# Power_HK.net
KiCad netlist of a schematic drawn in Altium Designer
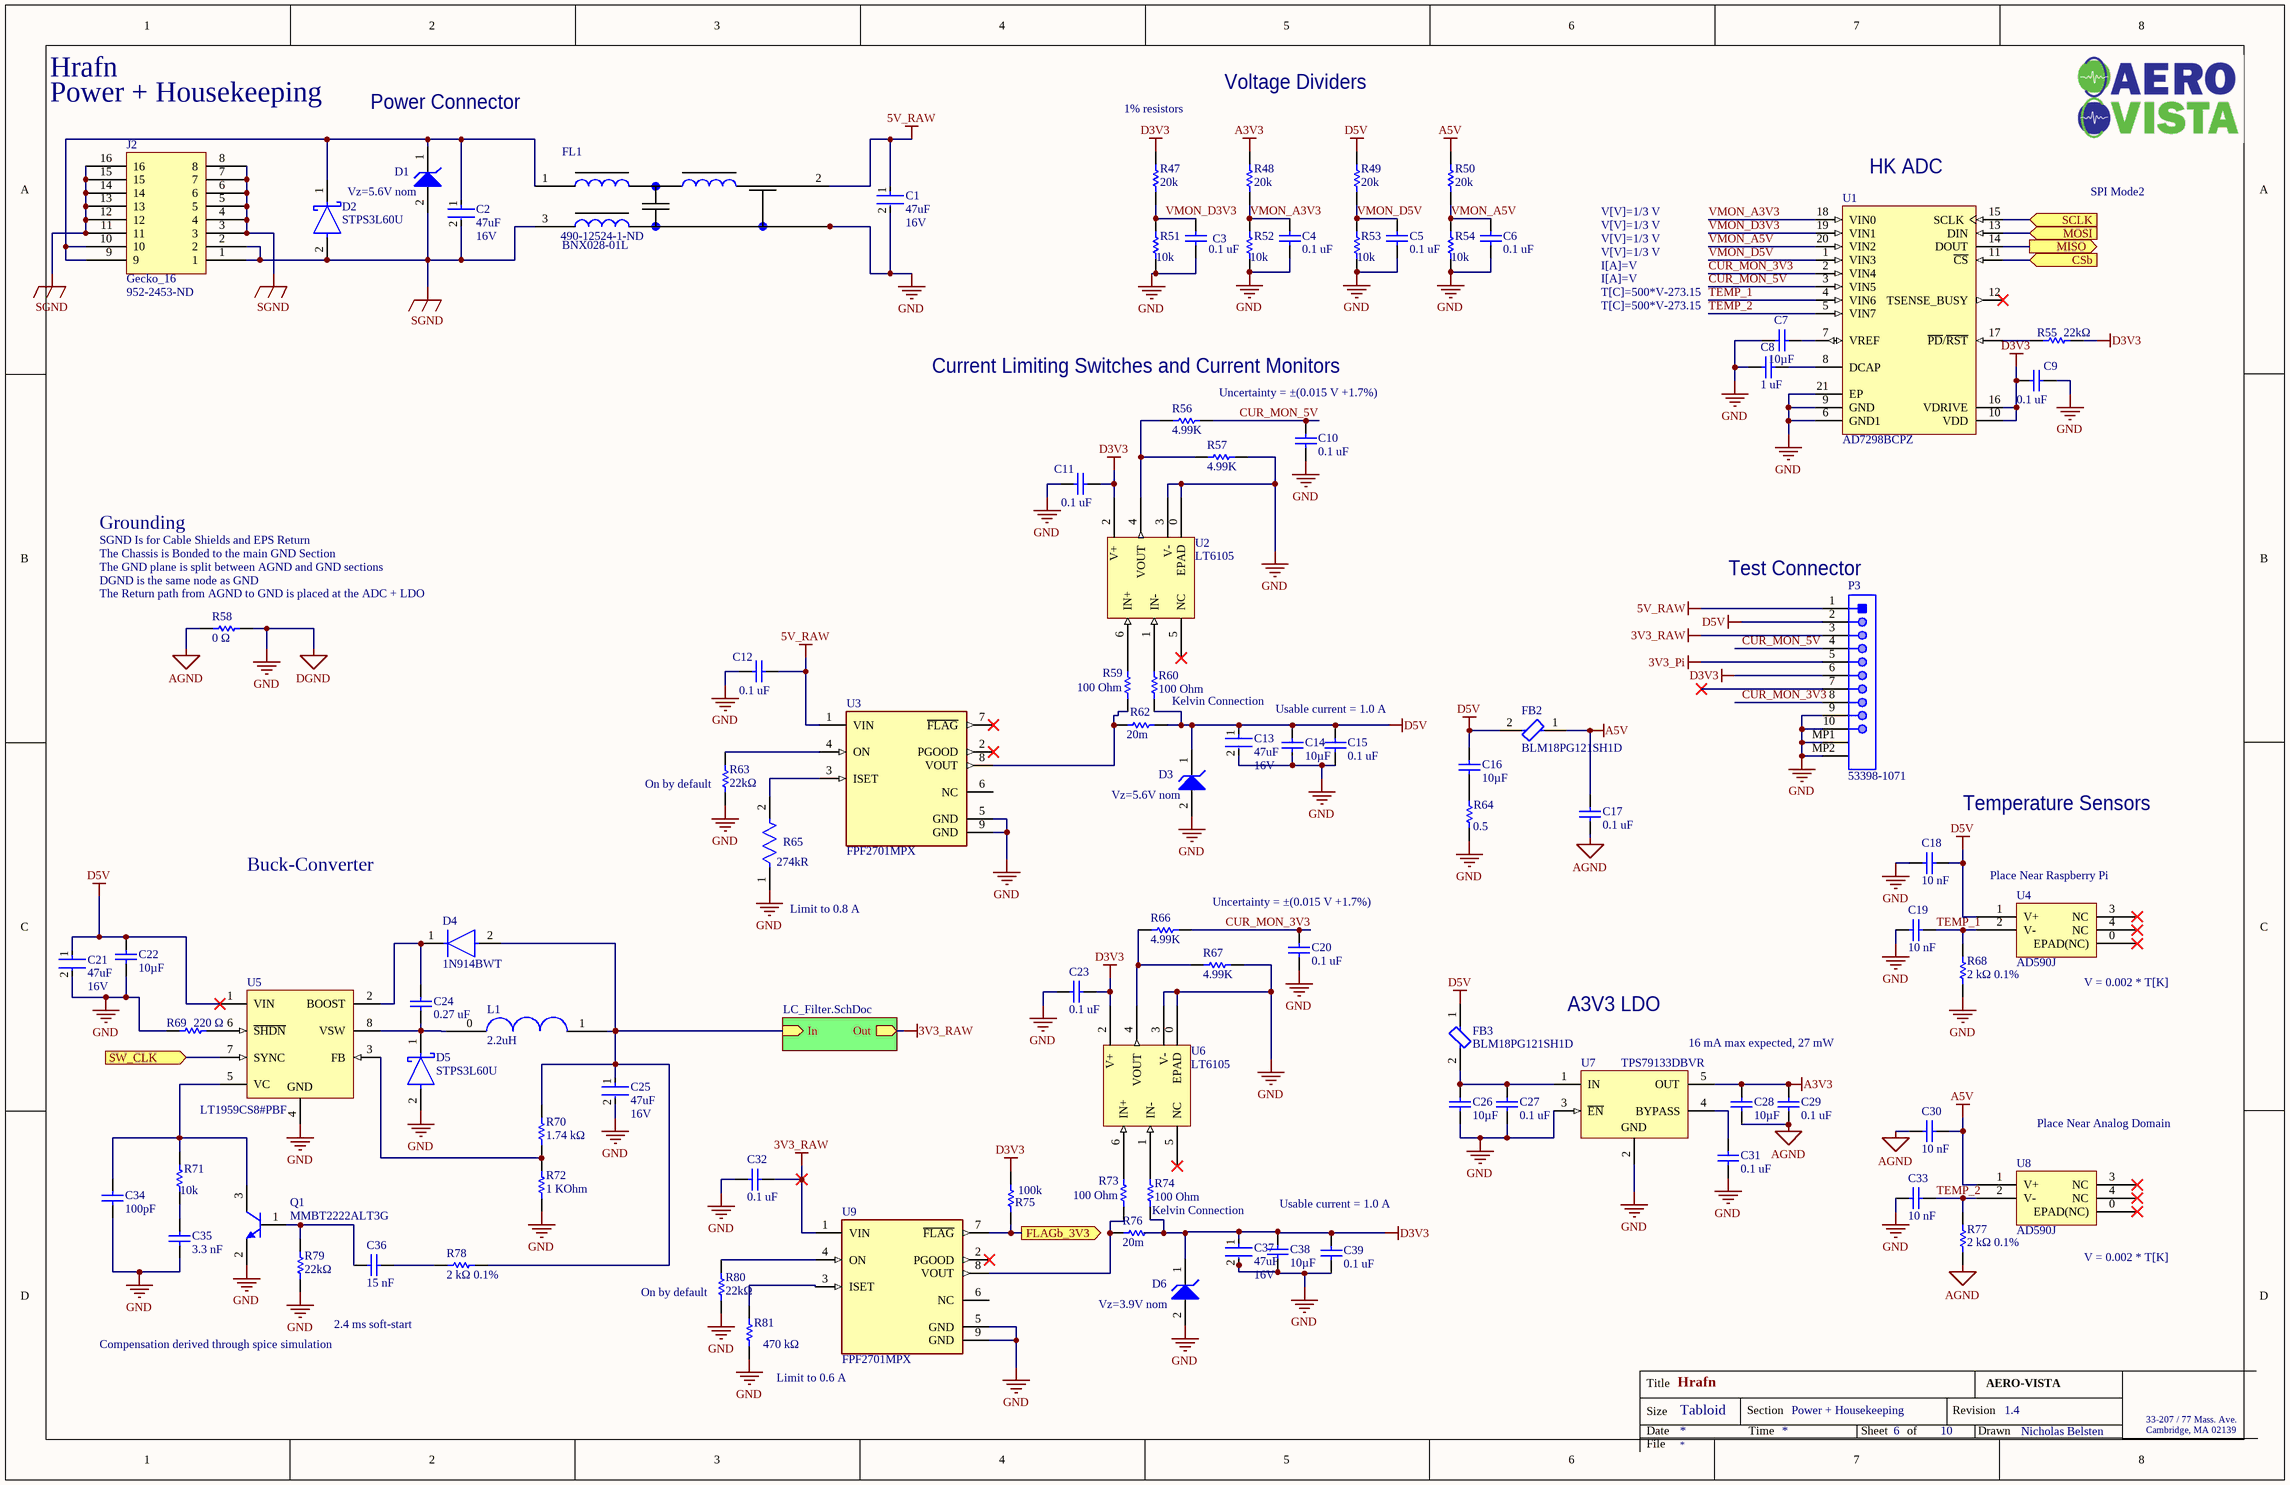
[diagram p0: Power_HK.SchDoc]

(export (version "E")
  (design (tool "Eeschema 10.0.6"))
  (components
    (comp (ref "C1")
      (value "GRT32EC81C476ME13L")
      (footprint "FP-GRT32E-0_3-IPC_C")
      (description "Multi-Layer Ceramic Capacitor 47uF 16V X6S ±20% 1210 Emboss T/R")
      (fields
        (field (name "CAPACITANCE") "47uF")
        (field (name "VOLTAGE RATING") "16V")
        (field (name "TOLERANCE") "20%")
      )
      (libsource (lib "Altium Content Vault") (part "02cd4be3c70576c341d710602a673aa"))
    )
    (comp (ref "C2")
      (value "GRT32EC81C476ME13L")
      (footprint "FP-GRT32E-0_3-IPC_C")
      (description "Multi-Layer Ceramic Capacitor 47uF 16V X6S ±20% 1210 Emboss T/R")
      (fields
        (field (name "CAPACITANCE") "47uF")
        (field (name "VOLTAGE RATING") "16V")
        (field (name "TOLERANCE") "20%")
      )
      (libsource (lib "Altium Content Vault") (part "02cd4be3c70576c341d710602a673aa"))
    )
    (comp (ref "C3")
      (value "0.1 uF")
      (footprint "CAPC0402(1005)60_L")
      (description "CAP 100nF 16V ±5% 0402 (1005 Metric) Thickness 0.6mm SMD")
      (fields (field (name "TOLERANCE") "Â±5%"))
      (libsource (lib "Altium Content Vault") (part "CAP"))
    )
    (comp (ref "C4")
      (value "0.1 uF")
      (footprint "CAPC0402(1005)60_L")
      (description "CAP 100nF 16V ±5% 0402 (1005 Metric) Thickness 0.6mm SMD")
      (fields (field (name "TOLERANCE") "Â±5%"))
      (libsource (lib "Altium Content Vault") (part "CAP"))
    )
    (comp (ref "C5")
      (value "0.1 uF")
      (footprint "CAPC0402(1005)60_L")
      (description "CAP 100nF 16V ±5% 0402 (1005 Metric) Thickness 0.6mm SMD")
      (fields (field (name "TOLERANCE") "Â±5%"))
      (libsource (lib "Altium Content Vault") (part "CAP"))
    )
    (comp (ref "C6")
      (value "0.1 uF")
      (footprint "CAPC0402(1005)60_L")
      (description "CAP 100nF 16V ±5% 0402 (1005 Metric) Thickness 0.6mm SMD")
      (fields (field (name "TOLERANCE") "Â±5%"))
      (libsource (lib "Altium Content Vault") (part "CAP"))
    )
    (comp (ref "C7")
      (value "EMK107BBJ106MA-T")
      (footprint "CAPC1608X100X35LL20T25")
      (description "Chip Capacitor, 10 uF, +/- 20%, 16 V, -55 to 85 degC, 0603 (1608 Metric), RoHS, Tape and Reel")
      (fields
        (field (name "CAPACITANCE") "10µF")
        (field (name "MANUFACTURER") "Taiyo Yuden")
        (field (name "TOLERANCE") "±20%")
      )
      (libsource (lib "Altium Content Vault") (part "CAP-NP-2"))
    )
    (comp (ref "C8")
      (value "1 uF")
      (footprint "CAPC1005X60X30NL05T10")
      (fields (field (name "PART NUMBER") "C0402C105M8PACTU") (field (name "MANUFACTURER") "Kemet"))
      (libsource (lib "Altium Content Vault") (part "CAP"))
    )
    (comp (ref "C9")
      (value "0.1 uF")
      (footprint "CAPC0402(1005)60_L")
      (description "CAP 100nF 16V ±5% 0402 (1005 Metric) Thickness 0.6mm SMD")
      (fields (field (name "TOLERANCE") "Â±5%"))
      (libsource (lib "Altium Content Vault") (part "CAP"))
    )
    (comp (ref "C10")
      (value "0.1 uF")
      (footprint "CAPC0402(1005)60_L")
      (description "CAP 100nF 16V ±5% 0402 (1005 Metric) Thickness 0.6mm SMD")
      (fields (field (name "TOLERANCE") "Â±5%"))
      (libsource (lib "Altium Content Vault") (part "CAP"))
    )
    (comp (ref "C11")
      (value "0.1 uF")
      (footprint "CAPC0402(1005)60_L")
      (description "CAP 100nF 16V ±5% 0402 (1005 Metric) Thickness 0.6mm SMD")
      (fields (field (name "TOLERANCE") "Â±5%"))
      (libsource (lib "Altium Content Vault") (part "CAP"))
    )
    (comp (ref "C12")
      (value "0.1 uF")
      (footprint "CAPC0402(1005)60_L")
      (description "CAP 100nF 16V ±5% 0402 (1005 Metric) Thickness 0.6mm SMD")
      (fields (field (name "TOLERANCE") "Â±5%"))
      (libsource (lib "Altium Content Vault") (part "CAP"))
    )
    (comp (ref "C13")
      (value "GRT32EC81C476ME13L")
      (footprint "FP-GRT32E-0_3-IPC_C")
      (description "Multi-Layer Ceramic Capacitor 47uF 16V X6S ±20% 1210 Emboss T/R")
      (fields
        (field (name "CAPACITANCE") "47uF")
        (field (name "VOLTAGE RATING") "16V")
        (field (name "TOLERANCE") "20%")
      )
      (libsource (lib "Altium Content Vault") (part "02cd4be3c70576c341d710602a673aa"))
    )
    (comp (ref "C14")
      (value "EMK107BBJ106MA-T")
      (footprint "CAPC1608X100X35LL20T25")
      (description "Chip Capacitor, 10 uF, +/- 20%, 16 V, -55 to 85 degC, 0603 (1608 Metric), RoHS, Tape and Reel")
      (fields
        (field (name "CAPACITANCE") "10µF")
        (field (name "MANUFACTURER") "Taiyo Yuden")
        (field (name "TOLERANCE") "±20%")
      )
      (libsource (lib "Altium Content Vault") (part "CAP-NP-2"))
    )
    (comp (ref "C15")
      (value "0.1 uF")
      (footprint "CAPC0402(1005)60_L")
      (description "CAP 100nF 16V ±5% 0402 (1005 Metric) Thickness 0.6mm SMD")
      (fields (field (name "TOLERANCE") "Â±5%"))
      (libsource (lib "Altium Content Vault") (part "CAP"))
    )
    (comp (ref "C16")
      (value "EMK107BBJ106MA-T")
      (footprint "CAPC1608X100X35LL20T25")
      (description "Chip Capacitor, 10 uF, +/- 20%, 16 V, -55 to 85 degC, 0603 (1608 Metric), RoHS, Tape and Reel")
      (fields
        (field (name "CAPACITANCE") "10µF")
        (field (name "MANUFACTURER") "Taiyo Yuden")
        (field (name "TOLERANCE") "±20%")
      )
      (libsource (lib "Altium Content Vault") (part "CAP-NP-2"))
    )
    (comp (ref "C17")
      (value "0.1 uF")
      (footprint "CAPC0402(1005)60_L")
      (description "CAP 100nF 16V ±5% 0402 (1005 Metric) Thickness 0.6mm SMD")
      (fields (field (name "TOLERANCE") "Â±5%"))
      (libsource (lib "Altium Content Vault") (part "CAP"))
    )
    (comp (ref "C18")
      (value "10 nF")
      (footprint "CAPC1005X56X25NL10T15")
      (fields
        (field (name "PART NUMBER") "0402ZC103KAT2A")
        (field (name "MANUFACTURER") "AVX Interconnect / Elco")
      )
      (libsource (lib "Altium Content Vault") (part "CAP"))
    )
    (comp (ref "C19")
      (value "10 nF")
      (footprint "CAPC1005X56X25NL10T15")
      (fields
        (field (name "PART NUMBER") "0402ZC103KAT2A")
        (field (name "MANUFACTURER") "AVX Interconnect / Elco")
      )
      (libsource (lib "Altium Content Vault") (part "CAP"))
    )
    (comp (ref "C20")
      (value "0.1 uF")
      (footprint "CAPC0402(1005)60_L")
      (description "CAP 100nF 16V ±5% 0402 (1005 Metric) Thickness 0.6mm SMD")
      (fields (field (name "TOLERANCE") "Â±5%"))
      (libsource (lib "Altium Content Vault") (part "CAP"))
    )
    (comp (ref "C21")
      (value "GRT32EC81C476ME13L")
      (footprint "FP-GRT32E-0_3-IPC_C")
      (description "Multi-Layer Ceramic Capacitor 47uF 16V X6S ±20% 1210 Emboss T/R")
      (fields
        (field (name "CAPACITANCE") "47uF")
        (field (name "VOLTAGE RATING") "16V")
        (field (name "TOLERANCE") "20%")
      )
      (libsource (lib "Altium Content Vault") (part "02cd4be3c70576c341d710602a673aa"))
    )
    (comp (ref "C22")
      (value "EMK107BBJ106MA-T")
      (footprint "CAPC1608X100X35LL20T25")
      (description "Chip Capacitor, 10 uF, +/- 20%, 16 V, -55 to 85 degC, 0603 (1608 Metric), RoHS, Tape and Reel")
      (fields
        (field (name "CAPACITANCE") "10µF")
        (field (name "MANUFACTURER") "Taiyo Yuden")
        (field (name "TOLERANCE") "±20%")
      )
      (libsource (lib "Altium Content Vault") (part "CAP-NP-2"))
    )
    (comp (ref "C23")
      (value "0.1 uF")
      (footprint "CAPC0402(1005)60_L")
      (description "CAP 100nF 16V ±5% 0402 (1005 Metric) Thickness 0.6mm SMD")
      (fields (field (name "TOLERANCE") "Â±5%"))
      (libsource (lib "Altium Content Vault") (part "CAP"))
    )
    (comp (ref "C24")
      (value "0.27 uF")
      (footprint "CAPC1005X55X25LL05T10")
      (fields (field (name "PART NUMBER") "GRM155R61A274KE15D") (field (name "MANUFACTURER") "Murata"))
      (libsource (lib "Altium Content Vault") (part "CAP"))
    )
    (comp (ref "C25")
      (value "GRT32EC81C476ME13L")
      (footprint "FP-GRT32E-0_3-IPC_C")
      (description "Multi-Layer Ceramic Capacitor 47uF 16V X6S ±20% 1210 Emboss T/R")
      (fields
        (field (name "CAPACITANCE") "47uF")
        (field (name "VOLTAGE RATING") "16V")
        (field (name "TOLERANCE") "20%")
      )
      (libsource (lib "Altium Content Vault") (part "02cd4be3c70576c341d710602a673aa"))
    )
    (comp (ref "C26")
      (value "EMK107BBJ106MA-T")
      (footprint "CAPC1608X100X35LL20T25")
      (description "Chip Capacitor, 10 uF, +/- 20%, 16 V, -55 to 85 degC, 0603 (1608 Metric), RoHS, Tape and Reel")
      (fields
        (field (name "CAPACITANCE") "10µF")
        (field (name "MANUFACTURER") "Taiyo Yuden")
        (field (name "TOLERANCE") "±20%")
      )
      (libsource (lib "Altium Content Vault") (part "CAP-NP-2"))
    )
    (comp (ref "C27")
      (value "0.1 uF")
      (footprint "CAPC0402(1005)60_L")
      (description "CAP 100nF 16V ±5% 0402 (1005 Metric) Thickness 0.6mm SMD")
      (fields (field (name "TOLERANCE") "Â±5%"))
      (libsource (lib "Altium Content Vault") (part "CAP"))
    )
    (comp (ref "C28")
      (value "EMK107BBJ106MA-T")
      (footprint "CAPC1608X100X35LL20T25")
      (description "Chip Capacitor, 10 uF, +/- 20%, 16 V, -55 to 85 degC, 0603 (1608 Metric), RoHS, Tape and Reel")
      (fields
        (field (name "CAPACITANCE") "10µF")
        (field (name "MANUFACTURER") "Taiyo Yuden")
        (field (name "TOLERANCE") "±20%")
      )
      (libsource (lib "Altium Content Vault") (part "CAP-NP-2"))
    )
    (comp (ref "C29")
      (value "0.1 uF")
      (footprint "CAPC0402(1005)60_L")
      (description "CAP 100nF 16V ±5% 0402 (1005 Metric) Thickness 0.6mm SMD")
      (fields (field (name "TOLERANCE") "Â±5%"))
      (libsource (lib "Altium Content Vault") (part "CAP"))
    )
    (comp (ref "C30")
      (value "10 nF")
      (footprint "CAPC1005X56X25NL10T15")
      (fields
        (field (name "PART NUMBER") "0402ZC103KAT2A")
        (field (name "MANUFACTURER") "AVX Interconnect / Elco")
      )
      (libsource (lib "Altium Content Vault") (part "CAP"))
    )
    (comp (ref "C31")
      (value "0.1 uF")
      (footprint "CAPC0402(1005)60_L")
      (description "CAP 100nF 16V ±5% 0402 (1005 Metric) Thickness 0.6mm SMD")
      (fields (field (name "TOLERANCE") "Â±5%"))
      (libsource (lib "Altium Content Vault") (part "CAP"))
    )
    (comp (ref "C32")
      (value "0.1 uF")
      (footprint "CAPC0402(1005)60_L")
      (description "CAP 100nF 16V ±5% 0402 (1005 Metric) Thickness 0.6mm SMD")
      (fields (field (name "TOLERANCE") "Â±5%"))
      (libsource (lib "Altium Content Vault") (part "CAP"))
    )
    (comp (ref "C33")
      (value "10 nF")
      (footprint "CAPC1005X56X25NL10T15")
      (fields
        (field (name "PART NUMBER") "0402ZC103KAT2A")
        (field (name "MANUFACTURER") "AVX Interconnect / Elco")
      )
      (libsource (lib "Altium Content Vault") (part "CAP"))
    )
    (comp (ref "C34")
      (value "100pF")
      (footprint "CAPC1005X55X25ML05T10")
      (fields (field (name "MANUFACTURER") "Murata") (field (name "PART NUMBER") "GRM1555C1H101JA01D"))
      (libsource (lib "Altium Content Vault") (part "CAP"))
    )
    (comp (ref "C35")
      (value "3.3 nF")
      (footprint "CAPC1005X56X25ML10T15")
      (fields
        (field (name "MANUFACTURER") "AVX Interconnect / Elco")
        (field (name "PART NUMBER") "04025C332JAT2A")
      )
      (libsource (lib "Altium Content Vault") (part "CAP"))
    )
    (comp (ref "C36")
      (value "15 nF")
      (footprint "CAPC1005X55X25NL05T10")
      (fields (field (name "PART NUMBER") "GRM155R71H153KA12J") (field (name "MANUFACTURER") "Murata"))
      (libsource (lib "Altium Content Vault") (part "CAP"))
    )
    (comp (ref "C37")
      (value "GRT32EC81C476ME13L")
      (footprint "FP-GRT32E-0_3-IPC_C")
      (description "Multi-Layer Ceramic Capacitor 47uF 16V X6S ±20% 1210 Emboss T/R")
      (fields
        (field (name "CAPACITANCE") "47uF")
        (field (name "VOLTAGE RATING") "16V")
        (field (name "TOLERANCE") "20%")
      )
      (libsource (lib "Altium Content Vault") (part "02cd4be3c70576c341d710602a673aa"))
    )
    (comp (ref "C38")
      (value "EMK107BBJ106MA-T")
      (footprint "CAPC1608X100X35LL20T25")
      (description "Chip Capacitor, 10 uF, +/- 20%, 16 V, -55 to 85 degC, 0603 (1608 Metric), RoHS, Tape and Reel")
      (fields
        (field (name "CAPACITANCE") "10µF")
        (field (name "MANUFACTURER") "Taiyo Yuden")
        (field (name "TOLERANCE") "±20%")
      )
      (libsource (lib "Altium Content Vault") (part "CAP-NP-2"))
    )
    (comp (ref "C39")
      (value "0.1 uF")
      (footprint "CAPC0402(1005)60_L")
      (description "CAP 100nF 16V ±5% 0402 (1005 Metric) Thickness 0.6mm SMD")
      (fields (field (name "TOLERANCE") "Â±5%"))
      (libsource (lib "Altium Content Vault") (part "CAP"))
    )
    (comp (ref "D1")
      (value "Vz=5.6V nom")
      (footprint "ONSC-SMA-2-403D-02_F_V")
      (description "1.5 W Zener Voltage Regulator, 2-Pin SMA, Pb-Free, Tape and Reel")
      (fields (field (name "PARTNUMBER") "SZ1SMA5919BT3G") (field (name "MANUFACTURER") "On Semiconductor"))
      (libsource (lib "Altium Content Vault") (part "ONSC-K1A2-2"))
    )
    (comp (ref "D2")
      (value "STPS3L60U")
      (footprint "FP-SMB-MFG")
      (description "DIODE SCHOTTKY 60V 3A SMB")
      (fields
        (field (name "OCTOPART") "https://octopart.com/stps3l60u-stmicroelectronics-334329")
        (field (name "MANUFACTURER") "STMicroelectronics")
      )
      (libsource (lib "Altium Content Vault") (part "fefb30dabb5d097ae2f038500735429"))
    )
    (comp (ref "D3")
      (value "Vz=5.6V nom")
      (footprint "ONSC-SMA-2-403D-02_F_V")
      (description "1.5 W Zener Voltage Regulator, 2-Pin SMA, Pb-Free, Tape and Reel")
      (fields (field (name "PARTNUMBER") "SZ1SMA5919BT3G") (field (name "MANUFACTURER") "On Semiconductor"))
      (libsource (lib "Altium Content Vault") (part "ONSC-K1A2-2"))
    )
    (comp (ref "D4")
      (value "1N914BWT")
      (footprint "FP-502-01-MFG")
      (description "DIODE GEN PURP 75V 200MA SOD523F")
      (fields
        (field (name "OCTOPART") "https://octopart.com/1n914bwt-on+semiconductor-84323166")
        (field (name "MANUFACTURER") "ON Semiconductor")
      )
      (libsource (lib "Altium Content Vault") (part "d7152d700b627762746794eb795d46e"))
    )
    (comp (ref "D5")
      (value "STPS3L60U")
      (footprint "FP-SMB-MFG")
      (description "DIODE SCHOTTKY 60V 3A SMB")
      (fields
        (field (name "OCTOPART") "https://octopart.com/stps3l60u-stmicroelectronics-334329")
        (field (name "MANUFACTURER") "STMicroelectronics")
      )
      (libsource (lib "Altium Content Vault") (part "fefb30dabb5d097ae2f038500735429"))
    )
    (comp (ref "D6")
      (value "Vz=3.9V nom")
      (footprint "ONSC-SMA-2-403D-02_F_V")
      (description "1.5 W Zener Voltage Regulator, 2-Pin SMA, Pb-Free, Tape and Reel")
      (fields (field (name "MANUFACTURER") "On Semiconductor") (field (name "PARTNUMBER") "1SMA5915BT3G"))
      (libsource (lib "Altium Content Vault") (part "ONSC-K1A2-2"))
    )
    (comp (ref "FB2")
      (value "BLM18PG121SH1D")
      (footprint "FP-BLM18-0_15-t0_8-IPC_C")
      (description "Chip Ferrite Bead, 0603, 120Ω @ 100MHz, 0.05Ω, 25%, 2A")
      (fields (field (name "TOLERANCE") "25%"))
      (libsource (lib "Altium Content Vault") (part "5f30dd21d616792df468990f7003faa"))
    )
    (comp (ref "FB3")
      (value "BLM18PG121SH1D")
      (footprint "FP-BLM18-0_15-t0_8-IPC_C")
      (description "Chip Ferrite Bead, 0603, 120Ω @ 100MHz, 0.05Ω, 25%, 2A")
      (fields (field (name "TOLERANCE") "25%"))
      (libsource (lib "Altium Content Vault") (part "5f30dd21d616792df468990f7003faa"))
    )
    (comp (ref "FL1")
      (value "BNX028-01L")
      (footprint "FIL_BNX028-01L - small")
      (description "FILTER LC 47UF SMD")
      (fields
        (field (name "DIGI-KEY_PART_NUMBER") "490-12524-1-ND")
        (field (name "MF") "Murata")
        (field (name "SUPPLIER PART NUMBER 1") "490-12524-1-ND")
      )
      (libsource (lib "Hrafn") (part "BNX028-01L"))
    )
    (comp (ref "J2")
      (value "Gecko_16")
      (footprint "GECK16")
      (description "Headers & Wire Housings 1.25MM M VERT 3.0MM 2X8 POS")
      (fields (field (name "SUPPLIER PART NUMBER 1") "952-2453-ND"))
      (libsource (lib "Hrafn") (part "Gecko_16"))
    )
    (comp (ref "L1")
      (value "L")
      (footprint "78438357022")
      (description "Power Inductor, Aec-Q200, 2.2Uh, 5.2A Rohs Compliant: Yes")
      (fields (field (name "INDUCTANCE") "2.2uH") (field (name "TOLERANCE") "20%"))
      (libsource (lib "Hrafn") (part "L"))
    )
    (comp (ref "P3")
      (value "53398-1071")
      (footprint "MOLX-53398-1071_V")
      (description "Male Header, Pitch 1.25 mm, 1 x 10 Position, Height 4.7 mm, -40 to 85 degC, RoHS, Tape and Reel")
      (fields (field (name "MANUFACTURER") "Molex"))
      (libsource (lib "Altium Content Vault") (part "CN-1P-2M-R10"))
    )
    (comp (ref "Q1")
      (value "MMBT2222ALT3G")
      (footprint "ONSC-SOT-23-3-318-08_V")
      (description "General Purpose Transistor, NPN Silicon, 3-Pin SOT-23, Pb-Free, Tape and Reel")
      (fields (field (name "MANUFACTURER") "On Semiconductor"))
      (libsource (lib "Altium Content Vault") (part "ONSC-NPN-B1E2C3-3"))
    )
    (comp (ref "R47")
      (value "RC0402FR-0720KL")
      (footprint "RESC1005X40X25LL05T10")
      (fields (field (name "MANUFACTURER") "Yageo / Phycomp") (field (name "RESISTANCE") "20k"))
      (libsource (lib "Altium Content Vault") (part "RES"))
    )
    (comp (ref "R48")
      (value "RC0402FR-0720KL")
      (footprint "RESC1005X40X25LL05T10")
      (fields (field (name "MANUFACTURER") "Yageo / Phycomp") (field (name "RESISTANCE") "20k"))
      (libsource (lib "Altium Content Vault") (part "RES"))
    )
    (comp (ref "R49")
      (value "RC0402FR-0720KL")
      (footprint "RESC1005X40X25LL05T10")
      (fields (field (name "MANUFACTURER") "Yageo / Phycomp") (field (name "RESISTANCE") "20k"))
      (libsource (lib "Altium Content Vault") (part "RES"))
    )
    (comp (ref "R50")
      (value "RC0402FR-0720KL")
      (footprint "RESC1005X40X25LL05T10")
      (fields (field (name "MANUFACTURER") "Yageo / Phycomp") (field (name "RESISTANCE") "20k"))
      (libsource (lib "Altium Content Vault") (part "RES"))
    )
    (comp (ref "R51")
      (value "CRCW040210K0FKEDHP")
      (footprint "RESC1005X40X25LL05T10")
      (fields (field (name "MANUFACTURER") "Vishay Dale") (field (name "RESISTANCE") "10k"))
      (libsource (lib "Altium Content Vault") (part "RES"))
    )
    (comp (ref "R52")
      (value "CRCW040210K0FKEDHP")
      (footprint "RESC1005X40X25LL05T10")
      (fields (field (name "MANUFACTURER") "Vishay Dale") (field (name "RESISTANCE") "10k"))
      (libsource (lib "Altium Content Vault") (part "RES"))
    )
    (comp (ref "R53")
      (value "CRCW040210K0FKEDHP")
      (footprint "RESC1005X40X25LL05T10")
      (fields (field (name "MANUFACTURER") "Vishay Dale") (field (name "RESISTANCE") "10k"))
      (libsource (lib "Altium Content Vault") (part "RES"))
    )
    (comp (ref "R54")
      (value "CRCW040210K0FKEDHP")
      (footprint "RESC1005X40X25LL05T10")
      (fields (field (name "MANUFACTURER") "Vishay Dale") (field (name "RESISTANCE") "10k"))
      (libsource (lib "Altium Content Vault") (part "RES"))
    )
    (comp (ref "R55")
      (value "22kΩ")
      (footprint "RESC1005X40X25LL05T05")
      (fields (field (name "MANUFACTURER") "Panasonic") (field (name "PART NUMBER") "ERJ-2GEJ223X"))
      (libsource (lib "Altium Content Vault") (part "RES"))
    )
    (comp (ref "R56")
      (value "4.99K")
      (footprint "RESC1005X40X25LL05T05")
      (description "Chip Resistor, 4.99 KOhm, +/- 1%, 100 mW, -55 to 155 degC, 0402 (1005 Metric), RoHS, Tape and Reel")
      (fields (field (name "MANUFACTURER") "Basic Passives") (field (name "TOLERANCE") "1%"))
      (libsource (lib "Altium Content Vault") (part "RES-2"))
    )
    (comp (ref "R57")
      (value "4.99K")
      (footprint "RESC1005X40X25LL05T05")
      (description "Chip Resistor, 4.99 KOhm, +/- 1%, 100 mW, -55 to 155 degC, 0402 (1005 Metric), RoHS, Tape and Reel")
      (fields (field (name "MANUFACTURER") "Basic Passives") (field (name "TOLERANCE") "1%"))
      (libsource (lib "Altium Content Vault") (part "RES-2"))
    )
    (comp (ref "R58")
      (value "AC0603JR-070RL")
      (footprint "RESC1608X55X25LL10T15")
      (fields (field (name "MANUFACTURER") "Yageo") (field (name "=RESISTANCE") "0 Ω"))
      (libsource (lib "Altium Content Vault") (part "RES"))
    )
    (comp (ref "R59")
      (value "ERJ-2RKF1000X")
      (footprint "RESC1005X40X25LL05T05")
      (description "Chip Resistor, 100 Ohm, +/- 1%, 100 mW, -55 to 155 degC, 0402 (1005 Metric), RoHS, Tape and Reel")
      (fields
        (field (name "MANUFACTURER") "Basic Passives")
        (field (name "TOLERANCE") "1%")
        (field (name "RESISTANCE") "100 Ohm")
      )
      (libsource (lib "Altium Content Vault") (part "RES-2"))
    )
    (comp (ref "R60")
      (value "ERJ-2RKF1000X")
      (footprint "RESC1005X40X25LL05T05")
      (description "Chip Resistor, 100 Ohm, +/- 1%, 100 mW, -55 to 155 degC, 0402 (1005 Metric), RoHS, Tape and Reel")
      (fields
        (field (name "MANUFACTURER") "Basic Passives")
        (field (name "TOLERANCE") "1%")
        (field (name "RESISTANCE") "100 Ohm")
      )
      (libsource (lib "Altium Content Vault") (part "RES-2"))
    )
    (comp (ref "R62")
      (value "20m")
      (footprint "RESC1608X55X25LL10T15")
      (fields (field (name "MANUFACTURER") "Yageo") (field (name "PART NUMBER") "RL0603FR-070R02L"))
      (libsource (lib "Altium Content Vault") (part "RES"))
    )
    (comp (ref "R63")
      (value "22kΩ")
      (footprint "RESC1005X40X25LL05T05")
      (fields (field (name "MANUFACTURER") "Panasonic") (field (name "PART NUMBER") "ERJ-2GEJ223X"))
      (libsource (lib "Altium Content Vault") (part "RES"))
    )
    (comp (ref "R64")
      (value "0.5")
      (footprint "RESC1005X40X25LL10T10")
      (fields (field (name "PART NUMBER") "RL0402FR-070R5L") (field (name "MANUFACTURER") "Yageo"))
      (libsource (lib "Altium Content Vault") (part "RES"))
    )
    (comp (ref "R65")
      (value "CRCW0402274KFKED")
      (footprint "FP-CRCW0402-e3-IPC_A")
      (description "RES Thick Film, 274kΩ, 1%, 0.063W, 100ppm/°C, 0402")
      (fields (field (name "TOLERANCE") "1%") (field (name "RESISTANCE") "274kR"))
      (libsource (lib "Altium Content Vault") (part "1029c3af85768c4190bb7ad29bc67b5"))
    )
    (comp (ref "R66")
      (value "4.99K")
      (footprint "RESC1005X40X25LL05T05")
      (description "Chip Resistor, 4.99 KOhm, +/- 1%, 100 mW, -55 to 155 degC, 0402 (1005 Metric), RoHS, Tape and Reel")
      (fields (field (name "MANUFACTURER") "Basic Passives") (field (name "TOLERANCE") "1%"))
      (libsource (lib "Altium Content Vault") (part "RES-2"))
    )
    (comp (ref "R67")
      (value "4.99K")
      (footprint "RESC1005X40X25LL05T05")
      (description "Chip Resistor, 4.99 KOhm, +/- 1%, 100 mW, -55 to 155 degC, 0402 (1005 Metric), RoHS, Tape and Reel")
      (fields (field (name "MANUFACTURER") "Basic Passives") (field (name "TOLERANCE") "1%"))
      (libsource (lib "Altium Content Vault") (part "RES-2"))
    )
    (comp (ref "R68")
      (value "2 kΩ 0.1%")
      (footprint "RESC1005X40X25LL10T10")
      (fields (field (name "MANUFACTURER") "Panasonic") (field (name "PART NUMBER") "ERA-2AEB202X"))
      (libsource (lib "Altium Content Vault") (part "RES"))
    )
    (comp (ref "R69")
      (value "220 Ω")
      (footprint "RESC1005X40X25LL05T05")
      (fields (field (name "PART NUMBER") "CRCW040220K0FKED") (field (name "MANUFACTURER") "Vishay Dale"))
      (libsource (lib "Altium Content Vault") (part "RES"))
    )
    (comp (ref "R70")
      (value "1.74 kΩ")
      (footprint "RESC1005X40X25NL05T10")
      (fields (field (name "PART NUMBER") "RC0402FR-071K74L") (field (name "MANUFACTURER") "Yageo"))
      (libsource (lib "Altium Content Vault") (part "RES"))
    )
    (comp (ref "R71")
      (value "CRCW040210K0FKEDHP")
      (footprint "RESC1005X40X25LL05T10")
      (fields (field (name "MANUFACTURER") "Vishay Dale") (field (name "RESISTANCE") "10k"))
      (libsource (lib "Altium Content Vault") (part "RES"))
    )
    (comp (ref "R72")
      (value "1 KOhm")
      (footprint "RESC1005X40X25NL05T05")
      (description "Chip Resistor, 1 KOhm, +/- 1%, 100 mW, -55 to 155 degC, 0402 (1005 Metric), RoHS, Tape and Reel")
      (fields (field (name "PARTNUMBER") "ERJ-2RKF1001X") (field (name "MANUFACTURER") "Basic Passives"))
      (libsource (lib "Altium Content Vault") (part "RES-2"))
    )
    (comp (ref "R73")
      (value "ERJ-2RKF1000X")
      (footprint "RESC1005X40X25LL05T05")
      (description "Chip Resistor, 100 Ohm, +/- 1%, 100 mW, -55 to 155 degC, 0402 (1005 Metric), RoHS, Tape and Reel")
      (fields
        (field (name "MANUFACTURER") "Basic Passives")
        (field (name "TOLERANCE") "1%")
        (field (name "RESISTANCE") "100 Ohm")
      )
      (libsource (lib "Altium Content Vault") (part "RES-2"))
    )
    (comp (ref "R74")
      (value "ERJ-2RKF1000X")
      (footprint "RESC1005X40X25LL05T05")
      (description "Chip Resistor, 100 Ohm, +/- 1%, 100 mW, -55 to 155 degC, 0402 (1005 Metric), RoHS, Tape and Reel")
      (fields
        (field (name "MANUFACTURER") "Basic Passives")
        (field (name "TOLERANCE") "1%")
        (field (name "RESISTANCE") "100 Ohm")
      )
      (libsource (lib "Altium Content Vault") (part "RES-2"))
    )
    (comp (ref "R75")
      (value "CRCW0402100KJNED")
      (footprint "RESC1005X40X25LL05T05")
      (fields (field (name "MANUFACTURER") "Vishay Dale") (field (name "RESISTANCE") "100k"))
      (libsource (lib "Altium Content Vault") (part "RES"))
    )
    (comp (ref "R76")
      (value "20m")
      (footprint "RESC1608X55X25LL10T15")
      (fields (field (name "MANUFACTURER") "Yageo") (field (name "PART NUMBER") "RL0603FR-070R02L"))
      (libsource (lib "Altium Content Vault") (part "RES"))
    )
    (comp (ref "R77")
      (value "2 kΩ 0.1%")
      (footprint "RESC1005X40X25LL10T10")
      (fields (field (name "MANUFACTURER") "Panasonic") (field (name "PART NUMBER") "ERA-2AEB202X"))
      (libsource (lib "Altium Content Vault") (part "RES"))
    )
    (comp (ref "R78")
      (value "2 kΩ 0.1%")
      (footprint "RESC1005X40X25LL10T10")
      (fields (field (name "MANUFACTURER") "Panasonic") (field (name "PART NUMBER") "ERA-2AEB202X"))
      (libsource (lib "Altium Content Vault") (part "RES"))
    )
    (comp (ref "R79")
      (value "22kΩ")
      (footprint "RESC1005X40X25LL05T05")
      (fields (field (name "MANUFACTURER") "Panasonic") (field (name "PART NUMBER") "ERJ-2GEJ223X"))
      (libsource (lib "Altium Content Vault") (part "RES"))
    )
    (comp (ref "R80")
      (value "22kΩ")
      (footprint "RESC1005X40X25LL05T05")
      (fields (field (name "MANUFACTURER") "Panasonic") (field (name "PART NUMBER") "ERJ-2GEJ223X"))
      (libsource (lib "Altium Content Vault") (part "RES"))
    )
    (comp (ref "R81")
      (value "ERJ2RKF4703X")
      (footprint "RESC1005X40X25LL05T05")
      (fields (field (name "MANUFACTURER") "Panasonic") (field (name "RESISTANCE") "470 kΩ"))
      (libsource (lib "Altium Content Vault") (part "RES"))
    )
    (comp (ref "U1")
      (value "AD7298BCPZ")
      (footprint "CP-20-8_M")
      (fields (field (name "MANUFACTURER") "Analog Devices") (field (name "GENERIC PART NUMBER") "AD7298"))
      (libsource (lib "Altium Content Vault") (part "ADI-AD7298-CP-20-8"))
    )
    (comp (ref "U2") (value "LT6105") (footprint "LT6105") (libsource (lib "Components") (part "LT6105")))
    (comp (ref "U3")
      (value "FPF2701MPX")
      (footprint "FP-511DD-MFG")
      (description "IC LOAD SWITCH 0.4-2A OCP 8MLP")
      (fields
        (field (name "OCTOPART") "https://octopart.com/fpf2701mpx-on+semiconductor-84327806")
        (field (name "MANUFACTURER") "ON Semiconductor")
      )
      (libsource (lib "Altium Content Vault") (part "acfcf82852ac67abfbd9dd99c9ad2d6"))
    )
    (comp (ref "U4") (value "AD590J") (footprint "DFN260P300X75-4N") (libsource (lib "Hrafn") (part "AD590")))
    (comp (ref "U5")
      (value "LT1959CS8#PBF")
      (footprint "LT-S8-8_L")
      (description "4.5 A, 500 kHz Step-Down Switching Regulator, 8-pin SOIC (S8-8), 0 to 125 degC, Pb-Free")
      (fields (field (name "MANUFACTURER") "Linear Technology"))
      (libsource (lib "Altium Content Vault") (part "LT-LT1959-S8-8"))
    )
    (comp (ref "U6") (value "LT6105") (footprint "LT6105") (libsource (lib "Components") (part "LT6105")))
    (comp (ref "U7")
      (value "TPS79133DBVR")
      (footprint "DBV0005A_N")
      (fields (field (name "MANUFACTURER") "Texas Instruments"))
      (libsource (lib "Altium Content Vault") (part "TI-TPS7XXXX-DBV5_A"))
    )
    (comp (ref "U8") (value "AD590J") (footprint "DFN260P300X75-4N") (libsource (lib "Hrafn") (part "AD590")))
    (comp (ref "U9")
      (value "FPF2701MPX")
      (footprint "FP-511DD-MFG")
      (description "IC LOAD SWITCH 0.4-2A OCP 8MLP")
      (fields
        (field (name "OCTOPART") "https://octopart.com/fpf2701mpx-on+semiconductor-84327806")
        (field (name "MANUFACTURER") "ON Semiconductor")
      )
      (libsource (lib "Altium Content Vault") (part "acfcf82852ac67abfbd9dd99c9ad2d6"))
    )
  )
  (nets
    (net (code "1") (name "/CSb") (class "Default")
      (node (ref "U1") (pin "11") (pinfunction "~{CS}_11") (pintype "input"))
    )
    (net (code "2") (name "/CUR_MON_3V3") (class "Default")
      (node (ref "C20") (pin "2") (pinfunction "2_2") (pintype "passive"))
      (node (ref "P3") (pin "8") (pinfunction "8_8") (pintype "passive"))
      (node (ref "R66") (pin "2") (pinfunction "2_2") (pintype "passive"))
      (node (ref "U1") (pin "2") (pinfunction "VIN4_2") (pintype "input"))
    )
    (net (code "3") (name "/CUR_MON_5V") (class "Default")
      (node (ref "C10") (pin "2") (pinfunction "2_2") (pintype "passive"))
      (node (ref "P3") (pin "4") (pinfunction "4_4") (pintype "passive"))
      (node (ref "R56") (pin "2") (pinfunction "2_2") (pintype "passive"))
      (node (ref "U1") (pin "3") (pinfunction "VIN5_3") (pintype "input"))
    )
    (net (code "4") (name "/FLAGb_3V3") (class "Default")
      (node (ref "R75") (pin "1") (pinfunction "1_1") (pintype "passive"))
      (node (ref "U9") (pin "7") (pinfunction "~{FLAG}_7") (pintype "output"))
    )
    (net (code "5") (name "/In") (class "Default")
      (node (ref "C25") (pin "1") (pinfunction "1_1") (pintype "passive"))
      (node (ref "D4") (pin "2") (pinfunction "A_2") (pintype "passive"))
      (node (ref "L1") (pin "1") (pinfunction "1_1") (pintype "passive"))
      (node (ref "R70") (pin "2") (pinfunction "2_2") (pintype "passive"))
      (node (ref "R78") (pin "1") (pinfunction "1_1") (pintype "passive"))
    )
    (net (code "6") (name "/MISO") (class "Default")
      (node (ref "U1") (pin "14") (pinfunction "DOUT_14") (pintype "tri_state"))
    )
    (net (code "7") (name "/MOSI") (class "Default")
      (node (ref "U1") (pin "13") (pinfunction "DIN_13") (pintype "input"))
    )
    (net (code "8") (name "/SCLK") (class "Default")
      (node (ref "U1") (pin "15") (pinfunction "SCLK_15") (pintype "input"))
    )
    (net (code "9") (name "/SW_CLK") (class "Default")
      (node (ref "U5") (pin "7") (pinfunction "SYNC_7") (pintype "input"))
    )
    (net (code "10") (name "/TEMP_1") (class "Default")
      (node (ref "C19") (pin "2") (pinfunction "2_2") (pintype "passive"))
      (node (ref "R68") (pin "2") (pinfunction "2_2") (pintype "passive"))
      (node (ref "U1") (pin "4") (pinfunction "VIN6_4") (pintype "input"))
      (node (ref "U4") (pin "2") (pinfunction "V-_2") (pintype "passive"))
    )
    (net (code "11") (name "/TEMP_2") (class "Default")
      (node (ref "C33") (pin "2") (pinfunction "2_2") (pintype "passive"))
      (node (ref "R77") (pin "2") (pinfunction "2_2") (pintype "passive"))
      (node (ref "U1") (pin "5") (pinfunction "VIN7_5") (pintype "input"))
      (node (ref "U8") (pin "2") (pinfunction "V-_2") (pintype "passive"))
    )
    (net (code "12") (name "/VMON_A3V3") (class "Default")
      (node (ref "C4") (pin "2") (pinfunction "2_2") (pintype "passive"))
      (node (ref "R48") (pin "1") (pinfunction "1_1") (pintype "passive"))
      (node (ref "R52") (pin "2") (pinfunction "2_2") (pintype "passive"))
      (node (ref "U1") (pin "18") (pinfunction "VIN0_18") (pintype "input"))
    )
    (net (code "13") (name "/VMON_A5V") (class "Default")
      (node (ref "C6") (pin "2") (pinfunction "2_2") (pintype "passive"))
      (node (ref "R50") (pin "1") (pinfunction "1_1") (pintype "passive"))
      (node (ref "R54") (pin "2") (pinfunction "2_2") (pintype "passive"))
      (node (ref "U1") (pin "20") (pinfunction "VIN2_20") (pintype "input"))
    )
    (net (code "14") (name "/VMON_D3V3") (class "Default")
      (node (ref "C3") (pin "2") (pinfunction "2_2") (pintype "passive"))
      (node (ref "R47") (pin "1") (pinfunction "1_1") (pintype "passive"))
      (node (ref "R51") (pin "2") (pinfunction "2_2") (pintype "passive"))
      (node (ref "U1") (pin "19") (pinfunction "VIN1_19") (pintype "input"))
    )
    (net (code "15") (name "/VMON_D5V") (class "Default")
      (node (ref "C5") (pin "2") (pinfunction "2_2") (pintype "passive"))
      (node (ref "R49") (pin "1") (pinfunction "1_1") (pintype "passive"))
      (node (ref "R53") (pin "2") (pinfunction "2_2") (pintype "passive"))
      (node (ref "U1") (pin "1") (pinfunction "VIN3_1") (pintype "input"))
    )
    (net (code "16") (name "3V3_Pi") (class "Default")
      (node (ref "P3") (pin "5") (pinfunction "5_5") (pintype "passive"))
    )
    (net (code "17") (name "3V3_RAW") (class "Default")
      (node (ref "C32") (pin "1") (pinfunction "1_1") (pintype "passive"))
      (node (ref "P3") (pin "3") (pinfunction "3_3") (pintype "passive"))
      (node (ref "U9") (pin "1") (pinfunction "VIN_1") (pintype "power_in"))
    )
    (net (code "18") (name "5V_RAW") (class "Default")
      (node (ref "C1") (pin "1") (pinfunction "1_1") (pintype "passive"))
      (node (ref "C12") (pin "2") (pinfunction "2_2") (pintype "passive"))
      (node (ref "FL1") (pin "2") (pinfunction "CB_2") (pintype "passive"))
      (node (ref "P3") (pin "1") (pinfunction "1_1") (pintype "passive"))
      (node (ref "U3") (pin "1") (pinfunction "VIN_1") (pintype "power_in"))
    )
    (net (code "19") (name "A3V3") (class "Default")
      (node (ref "C28") (pin "2") (pinfunction "2_2") (pintype "passive"))
      (node (ref "C29") (pin "2") (pinfunction "2_2") (pintype "passive"))
      (node (ref "R48") (pin "2") (pinfunction "2_2") (pintype "passive"))
      (node (ref "U7") (pin "5") (pinfunction "OUT_5") (pintype "power_in"))
    )
    (net (code "20") (name "A5V") (class "Default")
      (node (ref "C17") (pin "2") (pinfunction "2_2") (pintype "passive"))
      (node (ref "C30") (pin "2") (pinfunction "2_2") (pintype "passive"))
      (node (ref "FB2") (pin "1") (pinfunction "1_1") (pintype "passive"))
      (node (ref "R50") (pin "2") (pinfunction "2_2") (pintype "passive"))
      (node (ref "U8") (pin "1") (pinfunction "V+_1") (pintype "passive"))
    )
    (net (code "21") (name "AGND") (class "Default")
      (node (ref "C17") (pin "1") (pinfunction "1_1") (pintype "passive"))
      (node (ref "C28") (pin "1") (pinfunction "1_1") (pintype "passive"))
      (node (ref "C29") (pin "1") (pinfunction "1_1") (pintype "passive"))
      (node (ref "C30") (pin "1") (pinfunction "1_1") (pintype "passive"))
      (node (ref "R58") (pin "1") (pinfunction "1_1") (pintype "passive"))
      (node (ref "R77") (pin "1") (pinfunction "1_1") (pintype "passive"))
    )
    (net (code "22") (name "D3V3") (class "Default")
      (node (ref "C11") (pin "2") (pinfunction "2_2") (pintype "passive"))
      (node (ref "C23") (pin "1") (pinfunction "1_1") (pintype "passive"))
      (node (ref "C37") (pin "1") (pinfunction "1_1") (pintype "passive"))
      (node (ref "C38") (pin "2") (pinfunction "2_2") (pintype "passive"))
      (node (ref "C39") (pin "2") (pinfunction "2_2") (pintype "passive"))
      (node (ref "C9") (pin "1") (pinfunction "1_1") (pintype "passive"))
      (node (ref "D6") (pin "1") (pinfunction "K_1") (pintype "passive"))
      (node (ref "P3") (pin "6") (pinfunction "6_6") (pintype "passive"))
      (node (ref "R47") (pin "2") (pinfunction "2_2") (pintype "passive"))
      (node (ref "R55") (pin "2") (pinfunction "2_2") (pintype "passive"))
      (node (ref "R74") (pin "1") (pinfunction "1_1") (pintype "passive"))
      (node (ref "R75") (pin "2") (pinfunction "2_2") (pintype "passive"))
      (node (ref "R76") (pin "2") (pinfunction "2_2") (pintype "passive"))
      (node (ref "U1") (pin "10") (pinfunction "VDD_10") (pintype "power_in"))
      (node (ref "U1") (pin "16") (pinfunction "VDRIVE_16") (pintype "power_in"))
      (node (ref "U2") (pin "2") (pinfunction "V+_2") (pintype "power_in"))
      (node (ref "U6") (pin "2") (pinfunction "V+_2") (pintype "power_in"))
    )
    (net (code "23") (name "D5V") (class "Default")
      (node (ref "C13") (pin "1") (pinfunction "1_1") (pintype "passive"))
      (node (ref "C14") (pin "2") (pinfunction "2_2") (pintype "passive"))
      (node (ref "C15") (pin "2") (pinfunction "2_2") (pintype "passive"))
      (node (ref "C16") (pin "2") (pinfunction "2_2") (pintype "passive"))
      (node (ref "C18") (pin "2") (pinfunction "2_2") (pintype "passive"))
      (node (ref "C21") (pin "1") (pinfunction "1_1") (pintype "passive"))
      (node (ref "C22") (pin "2") (pinfunction "2_2") (pintype "passive"))
      (node (ref "D3") (pin "1") (pinfunction "K_1") (pintype "passive"))
      (node (ref "FB2") (pin "2") (pinfunction "2_2") (pintype "passive"))
      (node (ref "FB3") (pin "1") (pinfunction "1_1") (pintype "passive"))
      (node (ref "P3") (pin "2") (pinfunction "2_2") (pintype "passive"))
      (node (ref "R49") (pin "2") (pinfunction "2_2") (pintype "passive"))
      (node (ref "R60") (pin "1") (pinfunction "1_1") (pintype "passive"))
      (node (ref "R62") (pin "2") (pinfunction "2_2") (pintype "passive"))
      (node (ref "U4") (pin "1") (pinfunction "V+_1") (pintype "passive"))
      (node (ref "U5") (pin "1") (pinfunction "VIN_1") (pintype "power_in"))
    )
    (net (code "24") (name "DGND") (class "Default")
      (node (ref "C1") (pin "2") (pinfunction "2_2") (pintype "passive"))
      (node (ref "C10") (pin "1") (pinfunction "1_1") (pintype "passive"))
      (node (ref "C11") (pin "1") (pinfunction "1_1") (pintype "passive"))
      (node (ref "C12") (pin "1") (pinfunction "1_1") (pintype "passive"))
      (node (ref "C13") (pin "2") (pinfunction "2_2") (pintype "passive"))
      (node (ref "C14") (pin "1") (pinfunction "1_1") (pintype "passive"))
      (node (ref "C15") (pin "1") (pinfunction "1_1") (pintype "passive"))
      (node (ref "C18") (pin "1") (pinfunction "1_1") (pintype "passive"))
      (node (ref "C19") (pin "1") (pinfunction "1_1") (pintype "passive"))
      (node (ref "C20") (pin "1") (pinfunction "1_1") (pintype "passive"))
      (node (ref "C21") (pin "2") (pinfunction "2_2") (pintype "passive"))
      (node (ref "C22") (pin "1") (pinfunction "1_1") (pintype "passive"))
      (node (ref "C23") (pin "2") (pinfunction "2_2") (pintype "passive"))
      (node (ref "C25") (pin "2") (pinfunction "2_2") (pintype "passive"))
      (node (ref "C26") (pin "1") (pinfunction "1_1") (pintype "passive"))
      (node (ref "C27") (pin "1") (pinfunction "1_1") (pintype "passive"))
      (node (ref "C3") (pin "1") (pinfunction "1_1") (pintype "passive"))
      (node (ref "C31") (pin "1") (pinfunction "1_1") (pintype "passive"))
      (node (ref "C32") (pin "2") (pinfunction "2_2") (pintype "passive"))
      (node (ref "C33") (pin "1") (pinfunction "1_1") (pintype "passive"))
      (node (ref "C34") (pin "1") (pinfunction "1_1") (pintype "passive"))
      (node (ref "C35") (pin "1") (pinfunction "1_1") (pintype "passive"))
      (node (ref "C37") (pin "2") (pinfunction "2_2") (pintype "passive"))
      (node (ref "C38") (pin "1") (pinfunction "1_1") (pintype "passive"))
      (node (ref "C39") (pin "1") (pinfunction "1_1") (pintype "passive"))
      (node (ref "C4") (pin "1") (pinfunction "1_1") (pintype "passive"))
      (node (ref "C5") (pin "1") (pinfunction "1_1") (pintype "passive"))
      (node (ref "C6") (pin "1") (pinfunction "1_1") (pintype "passive"))
      (node (ref "C7") (pin "1") (pinfunction "1_1") (pintype "passive"))
      (node (ref "C8") (pin "2") (pinfunction "2_2") (pintype "passive"))
      (node (ref "C9") (pin "2") (pinfunction "2_2") (pintype "passive"))
      (node (ref "D3") (pin "2") (pinfunction "A_2") (pintype "passive"))
      (node (ref "D5") (pin "2") (pinfunction "A_2") (pintype "passive"))
      (node (ref "D6") (pin "2") (pinfunction "A_2") (pintype "passive"))
      (node (ref "FL1") (pin "4") (pinfunction "CG_4") (pintype "passive"))
      (node (ref "FL1") (pin "5") (pinfunction "CG_5") (pintype "passive"))
      (node (ref "FL1") (pin "6") (pinfunction "CG_6") (pintype "passive"))
      (node (ref "P3") (pin "10") (pinfunction "10_10") (pintype "passive"))
      (node (ref "P3") (pin "9") (pinfunction "9_9") (pintype "passive"))
      (node (ref "P3") (pin "MP1") (pinfunction "MP1_MP1") (pintype "passive"))
      (node (ref "P3") (pin "MP2") (pinfunction "MP2_MP2") (pintype "passive"))
      (node (ref "Q1") (pin "2") (pinfunction "E_2") (pintype "passive"))
      (node (ref "R51") (pin "1") (pinfunction "1_1") (pintype "passive"))
      (node (ref "R52") (pin "1") (pinfunction "1_1") (pintype "passive"))
      (node (ref "R53") (pin "1") (pinfunction "1_1") (pintype "passive"))
      (node (ref "R54") (pin "1") (pinfunction "1_1") (pintype "passive"))
      (node (ref "R57") (pin "2") (pinfunction "2_2") (pintype "passive"))
      (node (ref "R58") (pin "2") (pinfunction "2_2") (pintype "passive"))
      (node (ref "R63") (pin "1") (pinfunction "1_1") (pintype "passive"))
      (node (ref "R64") (pin "1") (pinfunction "1_1") (pintype "passive"))
      (node (ref "R65") (pin "1") (pinfunction "1_1") (pintype "passive"))
      (node (ref "R67") (pin "2") (pinfunction "2_2") (pintype "passive"))
      (node (ref "R68") (pin "1") (pinfunction "1_1") (pintype "passive"))
      (node (ref "R69") (pin "1") (pinfunction "1_1") (pintype "passive"))
      (node (ref "R72") (pin "1") (pinfunction "1_1") (pintype "passive"))
      (node (ref "R79") (pin "1") (pinfunction "1_1") (pintype "passive"))
      (node (ref "R80") (pin "1") (pinfunction "1_1") (pintype "passive"))
      (node (ref "R81") (pin "1") (pinfunction "1_1") (pintype "passive"))
      (node (ref "U1") (pin "21") (pinfunction "EP_21") (pintype "power_in"))
      (node (ref "U1") (pin "6") (pinfunction "GND1_6") (pintype "power_in"))
      (node (ref "U1") (pin "9") (pinfunction "GND_9") (pintype "power_in"))
      (node (ref "U2") (pin "0") (pinfunction "EPAD_0") (pintype "power_in"))
      (node (ref "U2") (pin "3") (pinfunction "V-_3") (pintype "power_in"))
      (node (ref "U3") (pin "5") (pinfunction "GND_5") (pintype "power_in"))
      (node (ref "U3") (pin "9") (pinfunction "GND_9") (pintype "power_in"))
      (node (ref "U5") (pin "4") (pinfunction "GND_4") (pintype "power_in"))
      (node (ref "U6") (pin "0") (pinfunction "EPAD_0") (pintype "power_in"))
      (node (ref "U6") (pin "3") (pinfunction "V-_3") (pintype "power_in"))
      (node (ref "U7") (pin "2") (pinfunction "GND_2") (pintype "power_in"))
      (node (ref "U7") (pin "3") (pinfunction "~{EN}_3") (pintype "input"))
      (node (ref "U9") (pin "5") (pinfunction "GND_5") (pintype "power_in"))
      (node (ref "U9") (pin "9") (pinfunction "GND_9") (pintype "power_in"))
    )
    (net (code "25") (name "Net-(C16-Pad1)") (class "Default")
      (node (ref "C16") (pin "1") (pinfunction "1_1") (pintype "passive"))
      (node (ref "R64") (pin "2") (pinfunction "2_2") (pintype "passive"))
    )
    (net (code "26") (name "Net-(C35-Pad2)") (class "Default")
      (node (ref "C35") (pin "2") (pinfunction "2_2") (pintype "passive"))
      (node (ref "R71") (pin "1") (pinfunction "1_1") (pintype "passive"))
    )
    (net (code "27") (name "Net-(C36-Pad2)") (class "Default")
      (node (ref "C36") (pin "2") (pinfunction "2_2") (pintype "passive"))
      (node (ref "R78") (pin "2") (pinfunction "2_2") (pintype "passive"))
    )
    (net (code "28") (name "Net-(D1-K)") (class "Default")
      (node (ref "C2") (pin "1") (pinfunction "1_1") (pintype "passive"))
      (node (ref "D1") (pin "1") (pinfunction "K_1") (pintype "passive"))
      (node (ref "D2") (pin "1") (pinfunction "K_1") (pintype "passive"))
      (node (ref "FL1") (pin "1") (pinfunction "B_1") (pintype "passive"))
      (node (ref "J2") (pin "10") (pinfunction "10_10") (pintype "passive"))
      (node (ref "J2") (pin "9") (pinfunction "9_9") (pintype "passive"))
    )
    (net (code "29") (name "Net-(D4-C)") (class "Default")
      (node (ref "C24") (pin "2") (pinfunction "2_2") (pintype "passive"))
      (node (ref "D4") (pin "1") (pinfunction "C_1") (pintype "passive"))
      (node (ref "U5") (pin "2") (pinfunction "BOOST_2") (pintype "passive"))
    )
    (net (code "30") (name "Net-(D5-K)") (class "Default")
      (node (ref "C24") (pin "1") (pinfunction "1_1") (pintype "passive"))
      (node (ref "D5") (pin "1") (pinfunction "K_1") (pintype "passive"))
      (node (ref "L1") (pin "0") (pinfunction "0_0") (pintype "passive"))
      (node (ref "U5") (pin "8") (pinfunction "VSW_8") (pintype "power_in"))
    )
    (net (code "31") (name "Net-(Q1-B)") (class "Default")
      (node (ref "C36") (pin "1") (pinfunction "1_1") (pintype "passive"))
      (node (ref "Q1") (pin "1") (pinfunction "B_1") (pintype "passive"))
      (node (ref "R79") (pin "2") (pinfunction "2_2") (pintype "passive"))
    )
    (net (code "32") (name "Net-(Q1-C)") (class "Default")
      (node (ref "C34") (pin "2") (pinfunction "2_2") (pintype "passive"))
      (node (ref "Q1") (pin "3") (pinfunction "C_3") (pintype "passive"))
      (node (ref "R71") (pin "2") (pinfunction "2_2") (pintype "passive"))
      (node (ref "U5") (pin "5") (pinfunction "VC_5") (pintype "passive"))
    )
    (net (code "33") (name "Net-(U1-DCAP)") (class "Default")
      (node (ref "C8") (pin "1") (pinfunction "1_1") (pintype "passive"))
      (node (ref "U1") (pin "8") (pinfunction "DCAP_8") (pintype "passive"))
    )
    (net (code "34") (name "Net-(U1-VREF)") (class "Default")
      (node (ref "C7") (pin "2") (pinfunction "2_2") (pintype "passive"))
      (node (ref "U1") (pin "7") (pinfunction "VREF_7") (pintype "bidirectional"))
    )
    (net (code "35") (name "Net-(U1-~{PD}{slash}~{RST})") (class "Default")
      (node (ref "R55") (pin "1") (pinfunction "1_1") (pintype "passive"))
      (node (ref "U1") (pin "17") (pinfunction "~{PD}/~{RST}_17") (pintype "input"))
    )
    (net (code "36") (name "Net-(U2-IN+)") (class "Default")
      (node (ref "R59") (pin "2") (pinfunction "2_2") (pintype "passive"))
      (node (ref "U2") (pin "6") (pinfunction "IN+_6") (pintype "input"))
    )
    (net (code "37") (name "Net-(U2-IN-)") (class "Default")
      (node (ref "R60") (pin "2") (pinfunction "2_2") (pintype "passive"))
      (node (ref "U2") (pin "1") (pinfunction "IN-_1") (pintype "input"))
    )
    (net (code "38") (name "Net-(U2-VOUT)") (class "Default")
      (node (ref "R56") (pin "1") (pinfunction "1_1") (pintype "passive"))
      (node (ref "R57") (pin "1") (pinfunction "1_1") (pintype "passive"))
      (node (ref "U2") (pin "4") (pinfunction "VOUT_4") (pintype "output"))
    )
    (net (code "39") (name "Net-(U3-ISET)") (class "Default")
      (node (ref "R65") (pin "2") (pinfunction "2_2") (pintype "passive"))
      (node (ref "U3") (pin "3") (pinfunction "ISET_3") (pintype "input"))
    )
    (net (code "40") (name "Net-(U3-ON)") (class "Default")
      (node (ref "R63") (pin "2") (pinfunction "2_2") (pintype "passive"))
      (node (ref "U3") (pin "4") (pinfunction "ON_4") (pintype "input"))
    )
    (net (code "41") (name "Net-(U3-VOUT)") (class "Default")
      (node (ref "R59") (pin "1") (pinfunction "1_1") (pintype "passive"))
      (node (ref "R62") (pin "1") (pinfunction "1_1") (pintype "passive"))
      (node (ref "U3") (pin "8") (pinfunction "VOUT_8") (pintype "output"))
    )
    (net (code "42") (name "Net-(U5-FB)") (class "Default")
      (node (ref "R70") (pin "1") (pinfunction "1_1") (pintype "passive"))
      (node (ref "R72") (pin "2") (pinfunction "2_2") (pintype "passive"))
      (node (ref "U5") (pin "3") (pinfunction "FB_3") (pintype "input"))
    )
    (net (code "43") (name "Net-(U5-~{SHDN})") (class "Default")
      (node (ref "R69") (pin "2") (pinfunction "2_2") (pintype "passive"))
      (node (ref "U5") (pin "6") (pinfunction "~{SHDN}_6") (pintype "input"))
    )
    (net (code "44") (name "Net-(U6-IN+)") (class "Default")
      (node (ref "R73") (pin "2") (pinfunction "2_2") (pintype "passive"))
      (node (ref "U6") (pin "6") (pinfunction "IN+_6") (pintype "input"))
    )
    (net (code "45") (name "Net-(U6-IN-)") (class "Default")
      (node (ref "R74") (pin "2") (pinfunction "2_2") (pintype "passive"))
      (node (ref "U6") (pin "1") (pinfunction "IN-_1") (pintype "input"))
    )
    (net (code "46") (name "Net-(U6-VOUT)") (class "Default")
      (node (ref "R66") (pin "1") (pinfunction "1_1") (pintype "passive"))
      (node (ref "R67") (pin "1") (pinfunction "1_1") (pintype "passive"))
      (node (ref "U6") (pin "4") (pinfunction "VOUT_4") (pintype "output"))
    )
    (net (code "47") (name "Net-(U7-BYPASS)") (class "Default")
      (node (ref "C31") (pin "2") (pinfunction "2_2") (pintype "passive"))
      (node (ref "U7") (pin "4") (pinfunction "BYPASS_4") (pintype "passive"))
    )
    (net (code "48") (name "Net-(U7-IN)") (class "Default")
      (node (ref "C26") (pin "2") (pinfunction "2_2") (pintype "passive"))
      (node (ref "C27") (pin "2") (pinfunction "2_2") (pintype "passive"))
      (node (ref "FB3") (pin "2") (pinfunction "2_2") (pintype "passive"))
      (node (ref "U7") (pin "1") (pinfunction "IN_1") (pintype "power_in"))
    )
    (net (code "49") (name "Net-(U9-ISET)") (class "Default")
      (node (ref "R81") (pin "2") (pinfunction "2_2") (pintype "passive"))
      (node (ref "U9") (pin "3") (pinfunction "ISET_3") (pintype "input"))
    )
    (net (code "50") (name "Net-(U9-ON)") (class "Default")
      (node (ref "R80") (pin "2") (pinfunction "2_2") (pintype "passive"))
      (node (ref "U9") (pin "4") (pinfunction "ON_4") (pintype "input"))
    )
    (net (code "51") (name "Net-(U9-VOUT)") (class "Default")
      (node (ref "R73") (pin "1") (pinfunction "1_1") (pintype "passive"))
      (node (ref "R76") (pin "1") (pinfunction "1_1") (pintype "passive"))
      (node (ref "U9") (pin "8") (pinfunction "VOUT_8") (pintype "output"))
    )
    (net (code "52") (name "SGND") (class "Default")
      (node (ref "C2") (pin "2") (pinfunction "2_2") (pintype "passive"))
      (node (ref "D1") (pin "2") (pinfunction "A_2") (pintype "passive"))
      (node (ref "D2") (pin "2") (pinfunction "A_2") (pintype "passive"))
      (node (ref "FL1") (pin "3") (pinfunction "PSG_3") (pintype "passive"))
      (node (ref "J2") (pin "1") (pinfunction "1_1") (pintype "passive"))
      (node (ref "J2") (pin "11") (pinfunction "11_11") (pintype "passive"))
      (node (ref "J2") (pin "12") (pinfunction "12_12") (pintype "passive"))
      (node (ref "J2") (pin "13") (pinfunction "13_13") (pintype "passive"))
      (node (ref "J2") (pin "14") (pinfunction "14_14") (pintype "passive"))
      (node (ref "J2") (pin "15") (pinfunction "15_15") (pintype "passive"))
      (node (ref "J2") (pin "16") (pinfunction "16_16") (pintype "passive"))
      (node (ref "J2") (pin "2") (pinfunction "2_2") (pintype "passive"))
      (node (ref "J2") (pin "3") (pinfunction "3_3") (pintype "passive"))
      (node (ref "J2") (pin "4") (pinfunction "4_4") (pintype "passive"))
      (node (ref "J2") (pin "5") (pinfunction "5_5") (pintype "passive"))
      (node (ref "J2") (pin "6") (pinfunction "6_6") (pintype "passive"))
      (node (ref "J2") (pin "7") (pinfunction "7_7") (pintype "passive"))
      (node (ref "J2") (pin "8") (pinfunction "8_8") (pintype "passive"))
    )
    (net (code "53") (name "unconnected-(P3-Pad7)") (class "Default")
      (node (ref "P3") (pin "7") (pinfunction "7_7") (pintype "passive+no_connect"))
    )
    (net (code "54") (name "unconnected-(U1-TSENSE_BUSY-Pad12)") (class "Default")
      (node (ref "U1") (pin "12") (pinfunction "TSENSE_BUSY_12") (pintype "output+no_connect"))
    )
    (net (code "55") (name "unconnected-(U2-NC-Pad5)") (class "Default")
      (node (ref "U2") (pin "5") (pinfunction "NC_5") (pintype "passive+no_connect"))
    )
    (net (code "56") (name "unconnected-(U3-NC-Pad6)") (class "Default")
      (node (ref "U3") (pin "6") (pinfunction "NC_6") (pintype "passive"))
    )
    (net (code "57") (name "unconnected-(U3-PGOOD-Pad2)") (class "Default")
      (node (ref "U3") (pin "2") (pinfunction "PGOOD_2") (pintype "output+no_connect"))
    )
    (net (code "58") (name "unconnected-(U3-~{FLAG}-Pad7)") (class "Default")
      (node (ref "U3") (pin "7") (pinfunction "~{FLAG}_7") (pintype "output+no_connect"))
    )
    (net (code "59") (name "unconnected-(U4-EPAD(NC)-Pad0)") (class "Default")
      (node (ref "U4") (pin "0") (pinfunction "EPAD(NC)_0") (pintype "passive+no_connect"))
    )
    (net (code "60") (name "unconnected-(U4-NC-Pad3)") (class "Default")
      (node (ref "U4") (pin "3") (pinfunction "NC_3") (pintype "passive+no_connect"))
    )
    (net (code "61") (name "unconnected-(U4-NC-Pad4)") (class "Default")
      (node (ref "U4") (pin "4") (pinfunction "NC_4") (pintype "passive+no_connect"))
    )
    (net (code "62") (name "unconnected-(U6-NC-Pad5)") (class "Default")
      (node (ref "U6") (pin "5") (pinfunction "NC_5") (pintype "passive+no_connect"))
    )
    (net (code "63") (name "unconnected-(U8-EPAD(NC)-Pad0)") (class "Default")
      (node (ref "U8") (pin "0") (pinfunction "EPAD(NC)_0") (pintype "passive+no_connect"))
    )
    (net (code "64") (name "unconnected-(U8-NC-Pad3)") (class "Default")
      (node (ref "U8") (pin "3") (pinfunction "NC_3") (pintype "passive+no_connect"))
    )
    (net (code "65") (name "unconnected-(U8-NC-Pad4)") (class "Default")
      (node (ref "U8") (pin "4") (pinfunction "NC_4") (pintype "passive+no_connect"))
    )
    (net (code "66") (name "unconnected-(U9-NC-Pad6)") (class "Default")
      (node (ref "U9") (pin "6") (pinfunction "NC_6") (pintype "passive"))
    )
    (net (code "67") (name "unconnected-(U9-PGOOD-Pad2)") (class "Default")
      (node (ref "U9") (pin "2") (pinfunction "PGOOD_2") (pintype "output+no_connect"))
    )
  )
)
